# amplifier-chain.net
KiCad netlist of a schematic drawn in Altium Designer
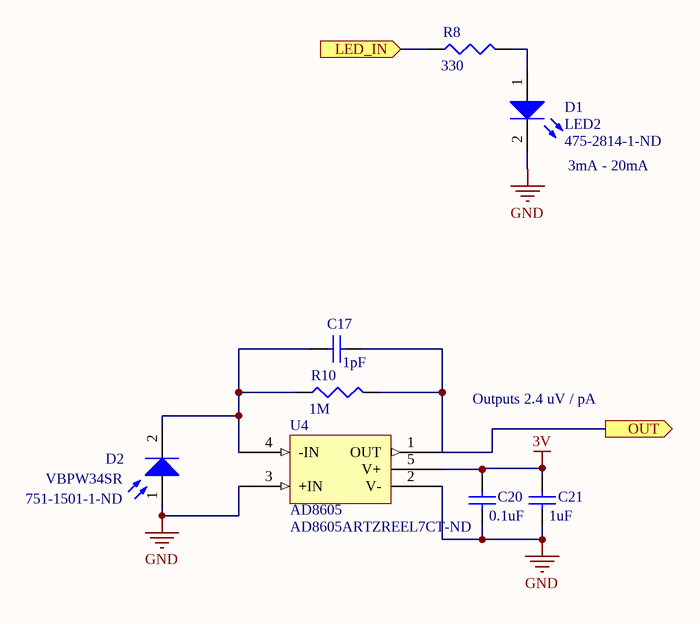
[diagram p0: amplifier-chain.SchDoc]

(export (version "E")
  (design (tool "Eeschema 10.0.6"))
  (components
    (comp (ref "C17")
      (value "1pF")
      (footprint "0402")
      (description "Capacitor (Semiconductor SIM Model)")
      (fields (field (name "PUBLISHER") "Altium Limited"))
      (libsource (lib "Miscellaneous Devices") (part "Cap Semi"))
    )
    (comp (ref "C20")
      (value "0.1uF")
      (footprint "0402")
      (description "Capacitor (Semiconductor SIM Model)")
      (fields (field (name "PUBLISHER") "Altium Limited"))
      (libsource (lib "Miscellaneous Devices") (part "Cap Semi"))
    )
    (comp (ref "C21")
      (value "1uF")
      (footprint "1608[0603]")
      (description "Capacitor (Semiconductor SIM Model)")
      (fields (field (name "PUBLISHER") "Altium Limited"))
      (libsource (lib "Miscellaneous Devices") (part "Cap Semi"))
    )
    (comp (ref "D1")
      (value "LED2")
      (footprint "LB P4SG")
      (description "Typical RED, GREEN, YELLOW, AMBER GaAs LED")
      (fields
        (field (name "SUPPLIER PART NUMBER") "475-2814-1-ND")
        (field (name "PUBLISHER") "Altium Limited")
      )
      (libsource (lib "Miscellaneous Devices") (part "LED2"))
    )
    (comp (ref "D2")
      (value "VBPW34SR")
      (footprint "VBPW34SR")
      (description "Photosensitive Diode")
      (fields
        (field (name "SUPPLIER PART NUMBER") "751-1501-1-ND")
        (field (name "PUBLISHER") "Altium Limited")
      )
      (libsource (lib "Miscellaneous Devices") (part "Photo Sen"))
    )
    (comp (ref "R8")
      (value "330")
      (footprint "0402")
      (description "Resistor")
      (fields (field (name "PUBLISHER") "Altium Limited"))
      (libsource (lib "Miscellaneous Devices") (part "Res3"))
    )
    (comp (ref "R10")
      (value "1M")
      (footprint "J1-0603")
      (description "Resistor")
      (fields (field (name "PUBLISHER") "Altium Limited"))
      (libsource (lib "Miscellaneous Devices") (part "Res3"))
    )
    (comp (ref "U4")
      (value "AD8605")
      (footprint "SOP-65P200X125-5N")
      (description "Low noise, precision rail-to-rail op-amp.")
      (fields (field (name "SUPPLIER PART NUMBER 1") "AD8605ARTZREEL7CT-ND"))
      (libsource (lib "PAY") (part "AD8605"))
    )
  )
  (nets
    (net (code "1") (name "/LED_IN") (class "Default")
      (node (ref "R8") (pin "1") (pinfunction "1_1") (pintype "passive"))
    )
    (net (code "2") (name "/OUT") (class "Default")
      (node (ref "C17") (pin "2") (pinfunction "2_2") (pintype "passive"))
      (node (ref "R10") (pin "2") (pinfunction "2_2") (pintype "passive"))
      (node (ref "U4") (pin "1") (pinfunction "OUT_1") (pintype "output"))
    )
    (net (code "3") (name "3V") (class "Default")
      (node (ref "C20") (pin "2") (pinfunction "2_2") (pintype "passive"))
      (node (ref "C21") (pin "2") (pinfunction "2_2") (pintype "passive"))
      (node (ref "U4") (pin "5") (pinfunction "V+_5") (pintype "power_in"))
    )
    (net (code "4") (name "GND") (class "Default")
      (node (ref "C20") (pin "1") (pinfunction "1_1") (pintype "passive"))
      (node (ref "C21") (pin "1") (pinfunction "1_1") (pintype "passive"))
      (node (ref "D1") (pin "2") (pinfunction "K_2") (pintype "passive"))
      (node (ref "D2") (pin "1") (pinfunction "A_1") (pintype "passive"))
      (node (ref "U4") (pin "2") (pinfunction "V-_2") (pintype "power_in"))
      (node (ref "U4") (pin "3") (pinfunction "+IN_3") (pintype "input"))
    )
    (net (code "5") (name "Net-(D1-A)") (class "Default")
      (node (ref "D1") (pin "1") (pinfunction "A_1") (pintype "passive"))
      (node (ref "R8") (pin "2") (pinfunction "2_2") (pintype "passive"))
    )
    (net (code "6") (name "Net-(D2-K)") (class "Default")
      (node (ref "C17") (pin "1") (pinfunction "1_1") (pintype "passive"))
      (node (ref "D2") (pin "2") (pinfunction "K_2") (pintype "passive"))
      (node (ref "R10") (pin "1") (pinfunction "1_1") (pintype "passive"))
      (node (ref "U4") (pin "4") (pinfunction "-IN_4") (pintype "input"))
    )
  )
)
